# v1_1_stm32.net
KiCad netlist of a schematic drawn in EasyEDA Pro
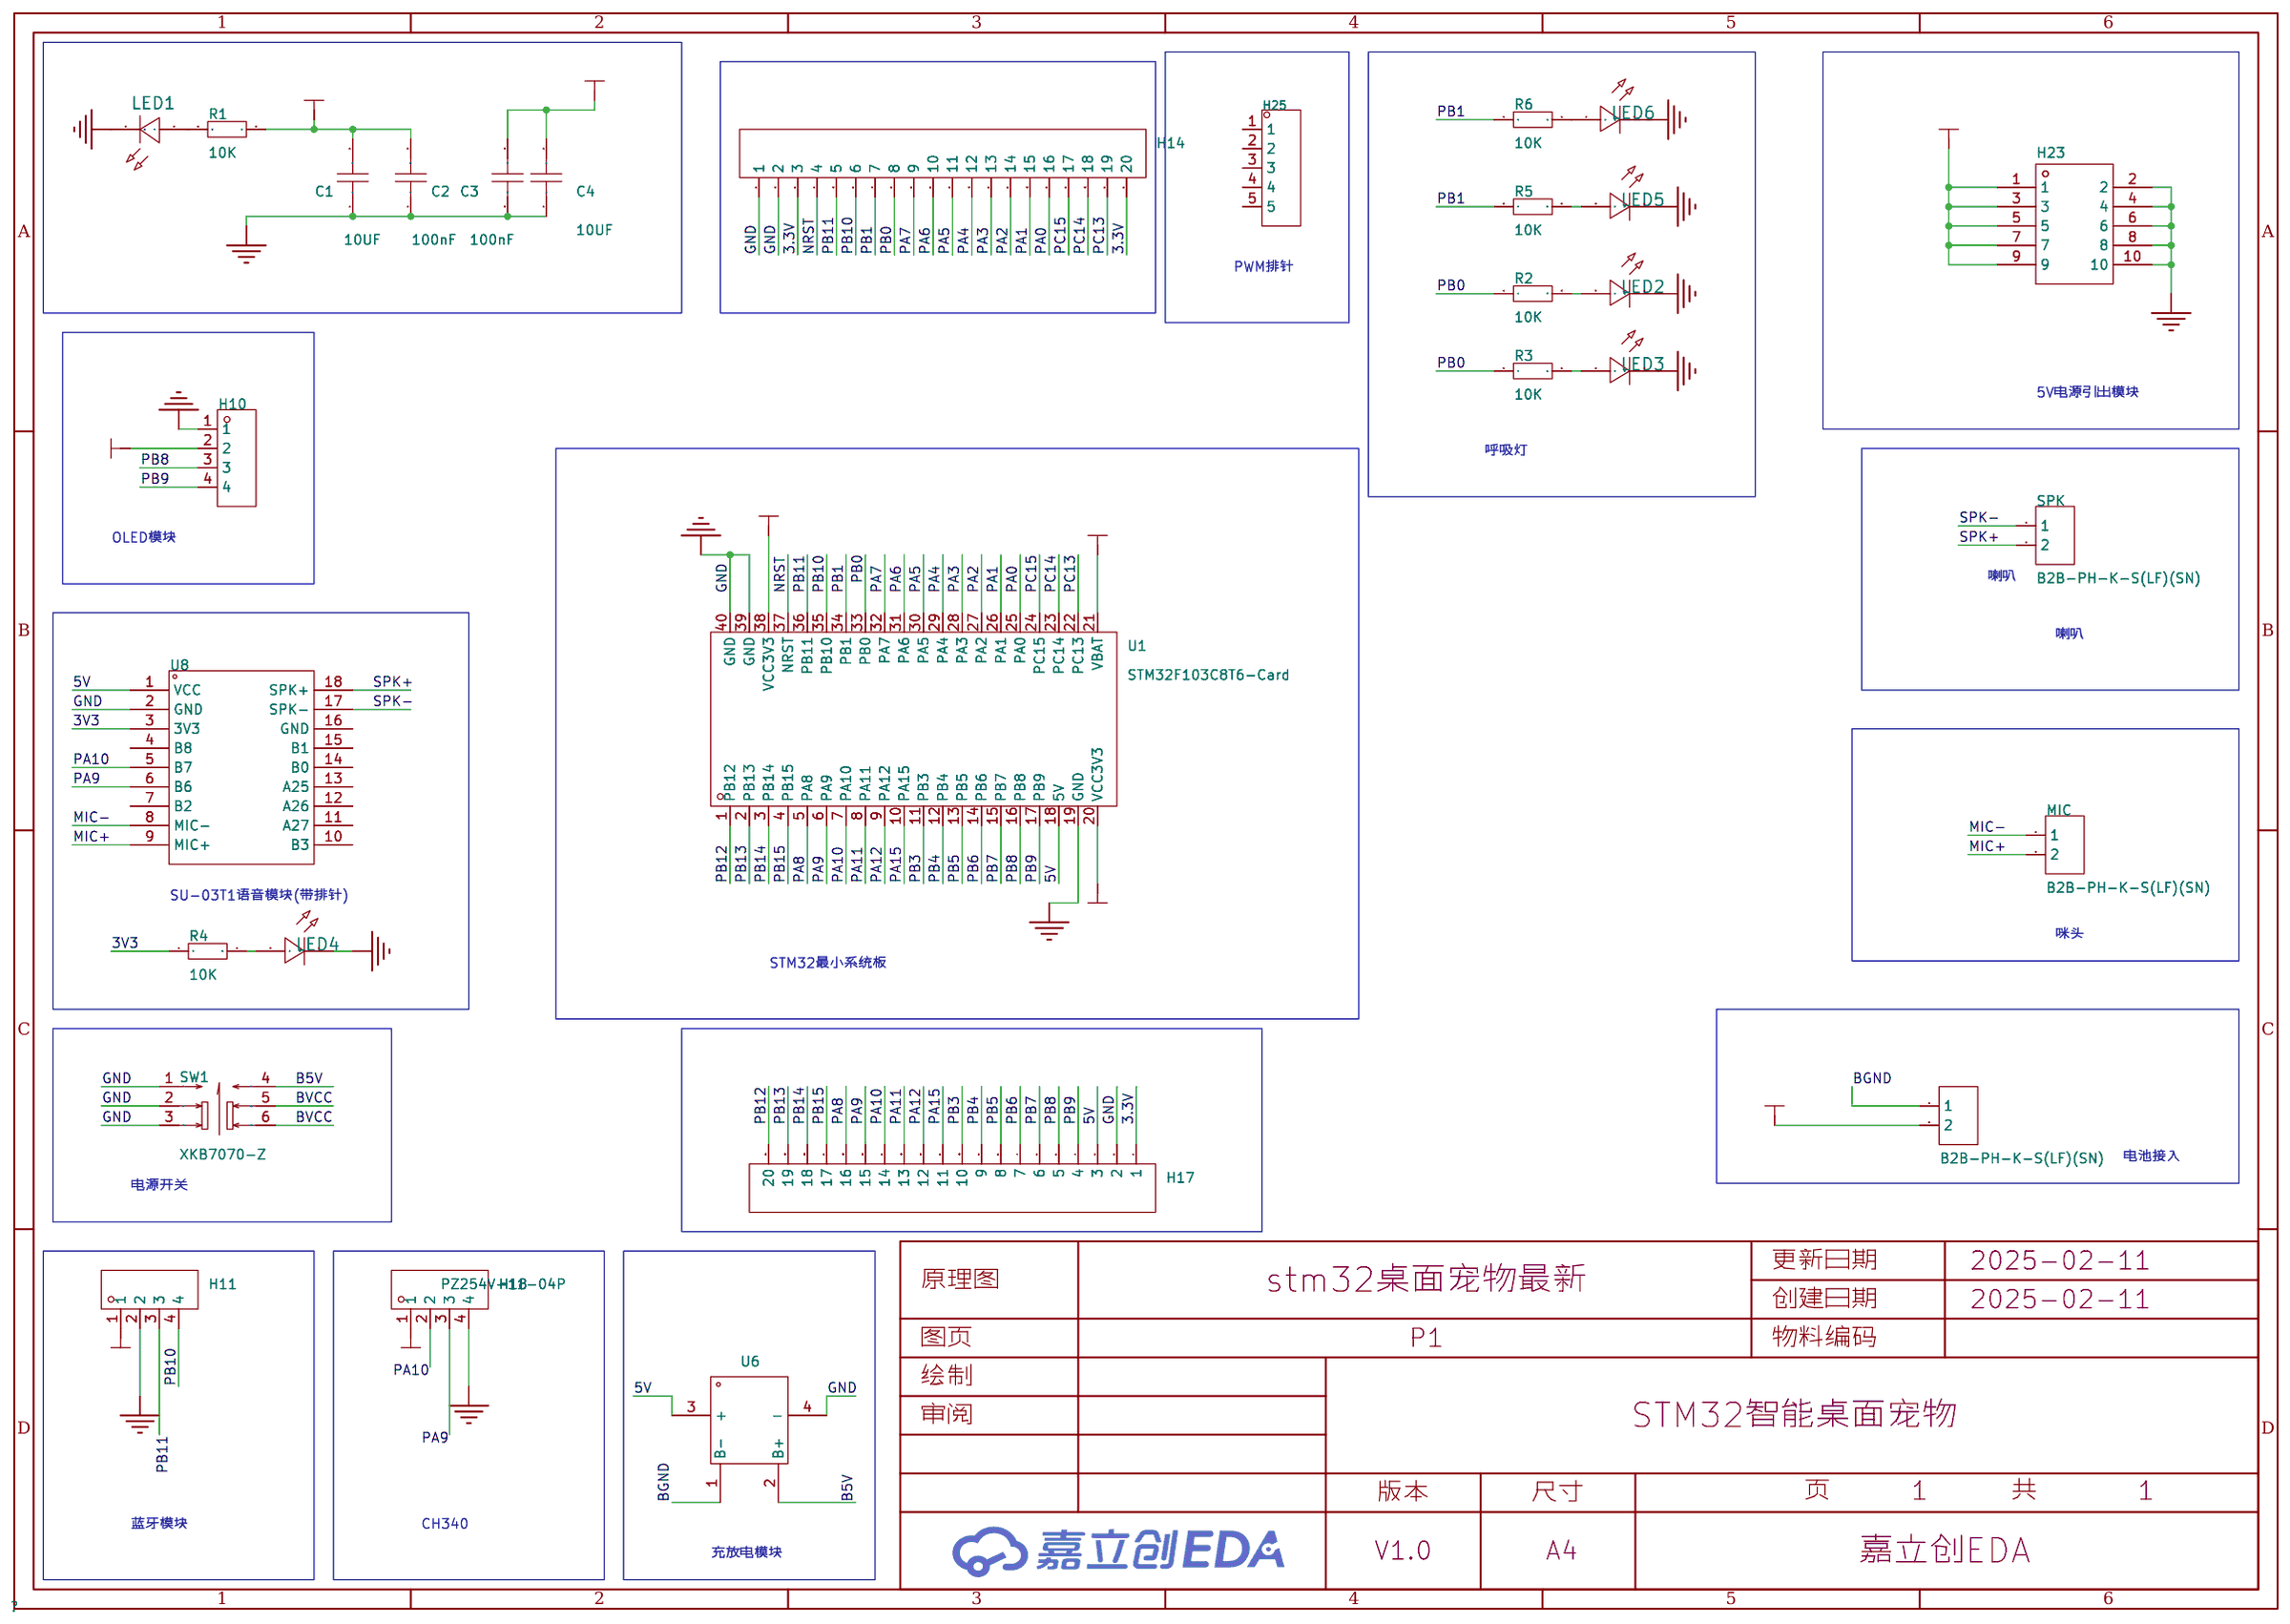
[diagram p0: schematic sheet]

(export (version "E")
  (design (tool "Eeschema 10.0.6"))
  (components
    (comp (ref "Battery")
      (value "B2B-PH-K-S(LF)(SN)")
      (fields (field (name "Manufacturer") "JST"))
      (libsource (lib "easyedapro") (part "Header-Female-2.54_1x2"))
    )
    (comp (ref "C1")
      (value "10UF")
      (footprint "easyedapro:C0805")
      (libsource (lib "easyedapro") (part "CapAcitance"))
    )
    (comp (ref "C2")
      (value "100nF")
      (footprint "easyedapro:C0805")
      (libsource (lib "easyedapro") (part "CapAcitance"))
    )
    (comp (ref "C3")
      (value "100nF")
      (footprint "easyedapro:C0805")
      (libsource (lib "easyedapro") (part "CapAcitance"))
    )
    (comp (ref "C4")
      (value "10UF")
      (footprint "easyedapro:C0805")
      (libsource (lib "easyedapro") (part "CapAcitance"))
    )
    (comp (ref "H10")
      (value "~")
      (footprint "easyedapro:HDR-TH_4P-P2.54-V-F")
      (libsource (lib "easyedapro") (part "2.54-1*4P母"))
    )
    (comp (ref "H11")
      (value "~")
      (footprint "easyedapro:HDR-TH_4P-P2.54-V-F")
      (libsource (lib "easyedapro") (part "2.54-1*4P母"))
    )
    (comp (ref "H14")
      (value "~")
      (footprint "easyedapro:HDR-TH_20P-P2.54-V-F")
      (libsource (lib "easyedapro") (part "HDR-F_2.54_1x20P"))
    )
    (comp (ref "H17")
      (value "~")
      (footprint "easyedapro:HDR-TH_20P-P2.54-V-F")
      (libsource (lib "easyedapro") (part "HDR-F_2.54_1x20P"))
    )
    (comp (ref "H18")
      (value "PZ254V-11-04P")
      (footprint "easyedapro:HDR-TH_4P-P2.54-V-F")
      (fields (field (name "Manufacturer") "XFCN(兴飞)"))
      (libsource (lib "easyedapro") (part "2.54-1*4P母"))
    )
    (comp (ref "H23")
      (value "~")
      (footprint "easyedapro:HDR-TH_10P-P2.54-V-M-R2-C5-S2.54")
      (libsource (lib "easyedapro") (part "HDR-M-2.54_2x5"))
    )
    (comp (ref "H25")
      (value "~")
      (footprint "easyedapro:HDR-TH_5P-P2.54-V-M")
      (libsource (lib "easyedapro") (part "MTP125-1105S1"))
    )
    (comp (ref "LED1")
      (value "~")
      (footprint "easyedapro:LED_0805")
      (libsource (lib "easyedapro") (part "LED_R"))
    )
    (comp (ref "LED2")
      (value "~")
      (footprint "easyedapro:LED_0805")
      (libsource (lib "easyedapro") (part "LED_R"))
    )
    (comp (ref "LED3")
      (value "~")
      (footprint "easyedapro:LED_0805")
      (libsource (lib "easyedapro") (part "LED_R"))
    )
    (comp (ref "LED4")
      (value "~")
      (footprint "easyedapro:LED_0805")
      (libsource (lib "easyedapro") (part "LED_R"))
    )
    (comp (ref "LED5")
      (value "~")
      (footprint "easyedapro:LED_0805")
      (libsource (lib "easyedapro") (part "LED_R"))
    )
    (comp (ref "LED6")
      (value "~")
      (footprint "easyedapro:LED_0805")
      (libsource (lib "easyedapro") (part "LED_R"))
    )
    (comp (ref "MIC")
      (value "B2B-PH-K-S(LF)(SN)")
      (fields (field (name "Manufacturer") "JST"))
      (libsource (lib "easyedapro") (part "Header-Female-2.54_1x2"))
    )
    (comp (ref "R1") (value "10K") (footprint "easyedapro:R0805") (libsource (lib "easyedapro") (part "电阻")))
    (comp (ref "R2") (value "10K") (footprint "easyedapro:R0805") (libsource (lib "easyedapro") (part "电阻")))
    (comp (ref "R3") (value "10K") (footprint "easyedapro:R0805") (libsource (lib "easyedapro") (part "电阻")))
    (comp (ref "R4") (value "10K") (footprint "easyedapro:R0805") (libsource (lib "easyedapro") (part "电阻")))
    (comp (ref "R5") (value "10K") (footprint "easyedapro:R0805") (libsource (lib "easyedapro") (part "电阻")))
    (comp (ref "R6") (value "10K") (footprint "easyedapro:R0805") (libsource (lib "easyedapro") (part "电阻")))
    (comp (ref "SPK")
      (value "B2B-PH-K-S(LF)(SN)")
      (fields (field (name "Manufacturer") "JST"))
      (libsource (lib "easyedapro") (part "Header-Female-2.54_1x2"))
    )
    (comp (ref "SW1")
      (value "XKB7070-Z")
      (footprint "easyedapro:SW-TH_6P-L7.0-W7.0-P2.00")
      (description "自锁/无锁:自锁;安装方式:直插;触点电流:100mA;额定电压 (AC):250V;额定电压 (DC):30V;带灯:不带;作用力:160gf;机械寿命:10万次;")
      (fields (field (name "Manufacturer") "XKB Connectivity(中国星坤)"))
      (libsource (lib "easyedapro") (part "XKB7070-Z"))
    )
    (comp (ref "U1")
      (value "STM32F103C8T6-Card")
      (footprint "easyedapro:CONN-TH_L53.3-W22.9_STM32F103C8T6-CARD")
      (libsource (lib "easyedapro") (part "STM32F103C8T6-CARD"))
    )
    (comp (ref "U6") (value "~") (libsource (lib "easyedapro") (part "5V充放电模块")))
    (comp (ref "U8")
      (value "~")
      (footprint "easyedapro:SU-03T带排针")
      (libsource (lib "easyedapro") (part "SU-03T带排针"))
    )
  )
  (nets
    (net (code "1") (name "/3V3") (class "Default")
      (node (ref "R4") (pin "1") (pinfunction "1_1") (pintype "input"))
      (node (ref "U8") (pin "3") (pinfunction "3V3_3") (pintype "input"))
    )
    (net (code "2") (name "/B5V") (class "Default")
      (node (ref "SW1") (pin "4") (pinfunction "4_4") (pintype "unspecified"))
      (node (ref "U6") (pin "2") (pinfunction "B+_2") (pintype "input"))
    )
    (net (code "3") (name "/BGND") (class "Default")
      (node (ref "Battery") (pin "1") (pinfunction "1_1") (pintype "input"))
      (node (ref "U6") (pin "1") (pinfunction "B-_1") (pintype "input"))
    )
    (net (code "4") (name "/MIC+") (class "Default")
      (node (ref "MIC") (pin "2") (pinfunction "2_2") (pintype "input"))
      (node (ref "U8") (pin "9") (pinfunction "MIC+_9") (pintype "input"))
    )
    (net (code "5") (name "/MIC-") (class "Default")
      (node (ref "MIC") (pin "1") (pinfunction "1_1") (pintype "input"))
      (node (ref "U8") (pin "8") (pinfunction "MIC-_8") (pintype "input"))
    )
    (net (code "6") (name "/NRST") (class "Default")
      (node (ref "H14") (pin "4") (pinfunction "4_4") (pintype "input"))
      (node (ref "U1") (pin "37") (pinfunction "NRST_37") (pintype "unspecified"))
    )
    (net (code "7") (name "/PA0") (class "Default")
      (node (ref "H14") (pin "16") (pinfunction "16_16") (pintype "input"))
      (node (ref "U1") (pin "25") (pinfunction "PA0_25") (pintype "unspecified"))
    )
    (net (code "8") (name "/PA1") (class "Default")
      (node (ref "H14") (pin "15") (pinfunction "15_15") (pintype "input"))
      (node (ref "U1") (pin "26") (pinfunction "PA1_26") (pintype "unspecified"))
    )
    (net (code "9") (name "/PA2") (class "Default")
      (node (ref "H14") (pin "14") (pinfunction "14_14") (pintype "input"))
      (node (ref "U1") (pin "27") (pinfunction "PA2_27") (pintype "unspecified"))
    )
    (net (code "10") (name "/PA3") (class "Default")
      (node (ref "H14") (pin "13") (pinfunction "13_13") (pintype "input"))
      (node (ref "U1") (pin "28") (pinfunction "PA3_28") (pintype "unspecified"))
    )
    (net (code "11") (name "/PA4") (class "Default")
      (node (ref "H14") (pin "12") (pinfunction "12_12") (pintype "input"))
      (node (ref "U1") (pin "29") (pinfunction "PA4_29") (pintype "unspecified"))
    )
    (net (code "12") (name "/PA5") (class "Default")
      (node (ref "H14") (pin "11") (pinfunction "11_11") (pintype "input"))
      (node (ref "U1") (pin "30") (pinfunction "PA5_30") (pintype "unspecified"))
    )
    (net (code "13") (name "/PA6") (class "Default")
      (node (ref "H14") (pin "10") (pinfunction "10_10") (pintype "input"))
      (node (ref "U1") (pin "31") (pinfunction "PA6_31") (pintype "unspecified"))
    )
    (net (code "14") (name "/PA7") (class "Default")
      (node (ref "H14") (pin "9") (pinfunction "9_9") (pintype "input"))
      (node (ref "U1") (pin "32") (pinfunction "PA7_32") (pintype "unspecified"))
    )
    (net (code "15") (name "/PA8") (class "Default")
      (node (ref "H17") (pin "16") (pinfunction "16_16") (pintype "input"))
      (node (ref "U1") (pin "5") (pinfunction "PA8_5") (pintype "unspecified"))
    )
    (net (code "16") (name "/PA9") (class "Default")
      (node (ref "H17") (pin "15") (pinfunction "15_15") (pintype "input"))
      (node (ref "H18") (pin "3") (pinfunction "3_3") (pintype "unspecified"))
      (node (ref "U1") (pin "6") (pinfunction "PA9_6") (pintype "unspecified"))
      (node (ref "U8") (pin "6") (pinfunction "B6_6") (pintype "input"))
    )
    (net (code "17") (name "/PA10") (class "Default")
      (node (ref "H17") (pin "14") (pinfunction "14_14") (pintype "input"))
      (node (ref "H18") (pin "2") (pinfunction "2_2") (pintype "unspecified"))
      (node (ref "U1") (pin "7") (pinfunction "PA10_7") (pintype "unspecified"))
      (node (ref "U8") (pin "5") (pinfunction "B7_5") (pintype "input"))
    )
    (net (code "18") (name "/PA11") (class "Default")
      (node (ref "H17") (pin "13") (pinfunction "13_13") (pintype "input"))
      (node (ref "U1") (pin "8") (pinfunction "PA11_8") (pintype "unspecified"))
    )
    (net (code "19") (name "/PA12") (class "Default")
      (node (ref "H17") (pin "12") (pinfunction "12_12") (pintype "input"))
      (node (ref "U1") (pin "9") (pinfunction "PA12_9") (pintype "unspecified"))
    )
    (net (code "20") (name "/PA15") (class "Default")
      (node (ref "H17") (pin "11") (pinfunction "11_11") (pintype "input"))
      (node (ref "U1") (pin "10") (pinfunction "PA15_10") (pintype "unspecified"))
    )
    (net (code "21") (name "/PB0") (class "Default")
      (node (ref "H14") (pin "8") (pinfunction "8_8") (pintype "input"))
      (node (ref "R2") (pin "1") (pinfunction "1_1") (pintype "input"))
      (node (ref "R3") (pin "1") (pinfunction "1_1") (pintype "input"))
      (node (ref "U1") (pin "33") (pinfunction "PB0_33") (pintype "unspecified"))
    )
    (net (code "22") (name "/PB1") (class "Default")
      (node (ref "H14") (pin "7") (pinfunction "7_7") (pintype "input"))
      (node (ref "R5") (pin "1") (pinfunction "1_1") (pintype "input"))
      (node (ref "R6") (pin "1") (pinfunction "1_1") (pintype "input"))
      (node (ref "U1") (pin "34") (pinfunction "PB1_34") (pintype "unspecified"))
    )
    (net (code "23") (name "/PB3") (class "Default")
      (node (ref "H17") (pin "10") (pinfunction "10_10") (pintype "input"))
      (node (ref "U1") (pin "11") (pinfunction "PB3_11") (pintype "unspecified"))
    )
    (net (code "24") (name "/PB4") (class "Default")
      (node (ref "H17") (pin "9") (pinfunction "9_9") (pintype "input"))
      (node (ref "U1") (pin "12") (pinfunction "PB4_12") (pintype "unspecified"))
    )
    (net (code "25") (name "/PB5") (class "Default")
      (node (ref "H17") (pin "8") (pinfunction "8_8") (pintype "input"))
      (node (ref "U1") (pin "13") (pinfunction "PB5_13") (pintype "unspecified"))
    )
    (net (code "26") (name "/PB6") (class "Default")
      (node (ref "H17") (pin "7") (pinfunction "7_7") (pintype "input"))
      (node (ref "U1") (pin "14") (pinfunction "PB6_14") (pintype "unspecified"))
    )
    (net (code "27") (name "/PB7") (class "Default")
      (node (ref "H17") (pin "6") (pinfunction "6_6") (pintype "input"))
      (node (ref "U1") (pin "15") (pinfunction "PB7_15") (pintype "unspecified"))
    )
    (net (code "28") (name "/PB8") (class "Default")
      (node (ref "H10") (pin "3") (pinfunction "3_3") (pintype "unspecified"))
      (node (ref "H17") (pin "5") (pinfunction "5_5") (pintype "input"))
      (node (ref "U1") (pin "16") (pinfunction "PB8_16") (pintype "unspecified"))
    )
    (net (code "29") (name "/PB9") (class "Default")
      (node (ref "H10") (pin "4") (pinfunction "4_4") (pintype "unspecified"))
      (node (ref "H17") (pin "4") (pinfunction "4_4") (pintype "input"))
      (node (ref "U1") (pin "17") (pinfunction "PB9_17") (pintype "unspecified"))
    )
    (net (code "30") (name "/PB10") (class "Default")
      (node (ref "H11") (pin "4") (pinfunction "4_4") (pintype "unspecified"))
      (node (ref "H14") (pin "6") (pinfunction "6_6") (pintype "input"))
      (node (ref "U1") (pin "35") (pinfunction "PB10_35") (pintype "unspecified"))
    )
    (net (code "31") (name "/PB11") (class "Default")
      (node (ref "H11") (pin "3") (pinfunction "3_3") (pintype "unspecified"))
      (node (ref "H14") (pin "5") (pinfunction "5_5") (pintype "input"))
      (node (ref "U1") (pin "36") (pinfunction "PB11_36") (pintype "unspecified"))
    )
    (net (code "32") (name "/PB12") (class "Default")
      (node (ref "H17") (pin "20") (pinfunction "20_20") (pintype "input"))
      (node (ref "U1") (pin "1") (pinfunction "PB12_1") (pintype "unspecified"))
    )
    (net (code "33") (name "/PB13") (class "Default")
      (node (ref "H17") (pin "19") (pinfunction "19_19") (pintype "input"))
      (node (ref "U1") (pin "2") (pinfunction "PB13_2") (pintype "unspecified"))
    )
    (net (code "34") (name "/PB14") (class "Default")
      (node (ref "H17") (pin "18") (pinfunction "18_18") (pintype "input"))
      (node (ref "U1") (pin "3") (pinfunction "PB14_3") (pintype "unspecified"))
    )
    (net (code "35") (name "/PB15") (class "Default")
      (node (ref "H17") (pin "17") (pinfunction "17_17") (pintype "input"))
      (node (ref "U1") (pin "4") (pinfunction "PB15_4") (pintype "unspecified"))
    )
    (net (code "36") (name "/PC13") (class "Default")
      (node (ref "H14") (pin "19") (pinfunction "19_19") (pintype "input"))
      (node (ref "U1") (pin "22") (pinfunction "PC13_22") (pintype "unspecified"))
    )
    (net (code "37") (name "/PC14") (class "Default")
      (node (ref "H14") (pin "18") (pinfunction "18_18") (pintype "input"))
      (node (ref "U1") (pin "23") (pinfunction "PC14_23") (pintype "unspecified"))
    )
    (net (code "38") (name "/PC15") (class "Default")
      (node (ref "H14") (pin "17") (pinfunction "17_17") (pintype "input"))
      (node (ref "U1") (pin "24") (pinfunction "PC15_24") (pintype "unspecified"))
    )
    (net (code "39") (name "/SPK+") (class "Default")
      (node (ref "SPK") (pin "2") (pinfunction "2_2") (pintype "input"))
      (node (ref "U8") (pin "18") (pinfunction "SPK+_18") (pintype "input"))
    )
    (net (code "40") (name "/SPK-") (class "Default")
      (node (ref "SPK") (pin "1") (pinfunction "1_1") (pintype "input"))
      (node (ref "U8") (pin "17") (pinfunction "SPK-_17") (pintype "input"))
    )
    (net (code "41") (name "3.3V") (class "Default")
      (node (ref "C3") (pin "2") (pinfunction "2_2") (pintype "input"))
      (node (ref "C4") (pin "2") (pinfunction "2_2") (pintype "input"))
      (node (ref "H10") (pin "2") (pinfunction "2_2") (pintype "unspecified"))
      (node (ref "H11") (pin "1") (pinfunction "1_1") (pintype "unspecified"))
      (node (ref "H14") (pin "20") (pinfunction "20_20") (pintype "input"))
      (node (ref "H14") (pin "3") (pinfunction "3_3") (pintype "input"))
      (node (ref "H17") (pin "1") (pinfunction "1_1") (pintype "input"))
      (node (ref "U1") (pin "20") (pinfunction "VCC3V3_20") (pintype "unspecified"))
      (node (ref "U1") (pin "21") (pinfunction "VBAT_21") (pintype "unspecified"))
      (node (ref "U1") (pin "38") (pinfunction "VCC3V3_38") (pintype "unspecified"))
    )
    (net (code "42") (name "5V") (class "Default")
      (node (ref "C1") (pin "2") (pinfunction "2_2") (pintype "input"))
      (node (ref "C2") (pin "2") (pinfunction "2_2") (pintype "input"))
      (node (ref "H17") (pin "3") (pinfunction "3_3") (pintype "input"))
      (node (ref "H18") (pin "1") (pinfunction "1_1") (pintype "unspecified"))
      (node (ref "H23") (pin "1") (pinfunction "1_1") (pintype "input"))
      (node (ref "H23") (pin "3") (pinfunction "3_3") (pintype "input"))
      (node (ref "H23") (pin "5") (pinfunction "5_5") (pintype "input"))
      (node (ref "H23") (pin "7") (pinfunction "7_7") (pintype "input"))
      (node (ref "H23") (pin "9") (pinfunction "9_9") (pintype "input"))
      (node (ref "R1") (pin "1") (pinfunction "1_1") (pintype "input"))
      (node (ref "U1") (pin "18") (pinfunction "5V_18") (pintype "unspecified"))
      (node (ref "U6") (pin "3") (pinfunction "+_3") (pintype "input"))
      (node (ref "U8") (pin "1") (pinfunction "VCC_1") (pintype "input"))
    )
    (net (code "43") (name "BVCC") (class "Default")
      (node (ref "Battery") (pin "2") (pinfunction "2_2") (pintype "input"))
      (node (ref "SW1") (pin "5") (pinfunction "5_5") (pintype "unspecified"))
      (node (ref "SW1") (pin "6") (pinfunction "6_6") (pintype "unspecified"))
    )
    (net (code "44") (name "GND") (class "Default")
      (node (ref "C1") (pin "1") (pinfunction "1_1") (pintype "input"))
      (node (ref "C2") (pin "1") (pinfunction "1_1") (pintype "input"))
      (node (ref "C3") (pin "1") (pinfunction "1_1") (pintype "input"))
      (node (ref "C4") (pin "1") (pinfunction "1_1") (pintype "input"))
      (node (ref "H10") (pin "1") (pinfunction "1_1") (pintype "unspecified"))
      (node (ref "H11") (pin "2") (pinfunction "2_2") (pintype "unspecified"))
      (node (ref "H14") (pin "1") (pinfunction "1_1") (pintype "input"))
      (node (ref "H14") (pin "2") (pinfunction "2_2") (pintype "input"))
      (node (ref "H17") (pin "2") (pinfunction "2_2") (pintype "input"))
      (node (ref "H18") (pin "4") (pinfunction "4_4") (pintype "unspecified"))
      (node (ref "H23") (pin "10") (pinfunction "10_10") (pintype "input"))
      (node (ref "H23") (pin "2") (pinfunction "2_2") (pintype "input"))
      (node (ref "H23") (pin "4") (pinfunction "4_4") (pintype "input"))
      (node (ref "H23") (pin "6") (pinfunction "6_6") (pintype "input"))
      (node (ref "H23") (pin "8") (pinfunction "8_8") (pintype "input"))
      (node (ref "LED1") (pin "1") (pinfunction "C_1") (pintype "input"))
      (node (ref "LED2") (pin "1") (pinfunction "C_1") (pintype "input"))
      (node (ref "LED3") (pin "1") (pinfunction "C_1") (pintype "input"))
      (node (ref "LED4") (pin "1") (pinfunction "C_1") (pintype "input"))
      (node (ref "LED5") (pin "1") (pinfunction "C_1") (pintype "input"))
      (node (ref "LED6") (pin "1") (pinfunction "C_1") (pintype "input"))
      (node (ref "SW1") (pin "1") (pinfunction "1_1") (pintype "unspecified"))
      (node (ref "SW1") (pin "2") (pinfunction "2_2") (pintype "unspecified"))
      (node (ref "SW1") (pin "3") (pinfunction "3_3") (pintype "unspecified"))
      (node (ref "U1") (pin "19") (pinfunction "GND_19") (pintype "unspecified"))
      (node (ref "U1") (pin "39") (pinfunction "GND_39") (pintype "unspecified"))
      (node (ref "U1") (pin "40") (pinfunction "GND_40") (pintype "unspecified"))
      (node (ref "U6") (pin "4") (pinfunction "-_4") (pintype "input"))
      (node (ref "U8") (pin "2") (pinfunction "GND_2") (pintype "input"))
    )
    (net (code "45") (name "Net-(LED1-A)") (class "Default")
      (node (ref "LED1") (pin "2") (pinfunction "A_2") (pintype "input"))
      (node (ref "R1") (pin "2") (pinfunction "2_2") (pintype "input"))
    )
    (net (code "46") (name "Net-(LED2-A)") (class "Default")
      (node (ref "LED2") (pin "2") (pinfunction "A_2") (pintype "input"))
      (node (ref "R2") (pin "2") (pinfunction "2_2") (pintype "input"))
    )
    (net (code "47") (name "Net-(LED3-A)") (class "Default")
      (node (ref "LED3") (pin "2") (pinfunction "A_2") (pintype "input"))
      (node (ref "R3") (pin "2") (pinfunction "2_2") (pintype "input"))
    )
    (net (code "48") (name "Net-(LED4-A)") (class "Default")
      (node (ref "LED4") (pin "2") (pinfunction "A_2") (pintype "input"))
      (node (ref "R4") (pin "2") (pinfunction "2_2") (pintype "input"))
    )
    (net (code "49") (name "Net-(LED5-A)") (class "Default")
      (node (ref "LED5") (pin "2") (pinfunction "A_2") (pintype "input"))
      (node (ref "R5") (pin "2") (pinfunction "2_2") (pintype "input"))
    )
    (net (code "50") (name "Net-(LED6-A)") (class "Default")
      (node (ref "LED6") (pin "2") (pinfunction "A_2") (pintype "input"))
      (node (ref "R6") (pin "2") (pinfunction "2_2") (pintype "input"))
    )
    (net (code "51") (name "unconnected-(H25-Pad1)") (class "Default")
      (node (ref "H25") (pin "1") (pinfunction "1_1") (pintype "input"))
    )
    (net (code "52") (name "unconnected-(H25-Pad2)") (class "Default")
      (node (ref "H25") (pin "2") (pinfunction "2_2") (pintype "input"))
    )
    (net (code "53") (name "unconnected-(H25-Pad3)") (class "Default")
      (node (ref "H25") (pin "3") (pinfunction "3_3") (pintype "input"))
    )
    (net (code "54") (name "unconnected-(H25-Pad4)") (class "Default")
      (node (ref "H25") (pin "4") (pinfunction "4_4") (pintype "input"))
    )
    (net (code "55") (name "unconnected-(H25-Pad5)") (class "Default")
      (node (ref "H25") (pin "5") (pinfunction "5_5") (pintype "input"))
    )
    (net (code "56") (name "unconnected-(U8-A25-Pad13)") (class "Default")
      (node (ref "U8") (pin "13") (pinfunction "A25_13") (pintype "input"))
    )
    (net (code "57") (name "unconnected-(U8-A26-Pad12)") (class "Default")
      (node (ref "U8") (pin "12") (pinfunction "A26_12") (pintype "input"))
    )
    (net (code "58") (name "unconnected-(U8-A27-Pad11)") (class "Default")
      (node (ref "U8") (pin "11") (pinfunction "A27_11") (pintype "input"))
    )
    (net (code "59") (name "unconnected-(U8-B0-Pad14)") (class "Default")
      (node (ref "U8") (pin "14") (pinfunction "B0_14") (pintype "input"))
    )
    (net (code "60") (name "unconnected-(U8-B1-Pad15)") (class "Default")
      (node (ref "U8") (pin "15") (pinfunction "B1_15") (pintype "input"))
    )
    (net (code "61") (name "unconnected-(U8-B2-Pad7)") (class "Default")
      (node (ref "U8") (pin "7") (pinfunction "B2_7") (pintype "input"))
    )
    (net (code "62") (name "unconnected-(U8-B3-Pad10)") (class "Default")
      (node (ref "U8") (pin "10") (pinfunction "B3_10") (pintype "input"))
    )
    (net (code "63") (name "unconnected-(U8-B8-Pad4)") (class "Default")
      (node (ref "U8") (pin "4") (pinfunction "B8_4") (pintype "input"))
    )
    (net (code "64") (name "unconnected-(U8-GND-Pad16)") (class "Default")
      (node (ref "U8") (pin "16") (pinfunction "GND_16") (pintype "input"))
    )
  )
)
